# WiFi.net
KiCad netlist of a schematic drawn in Altium Designer
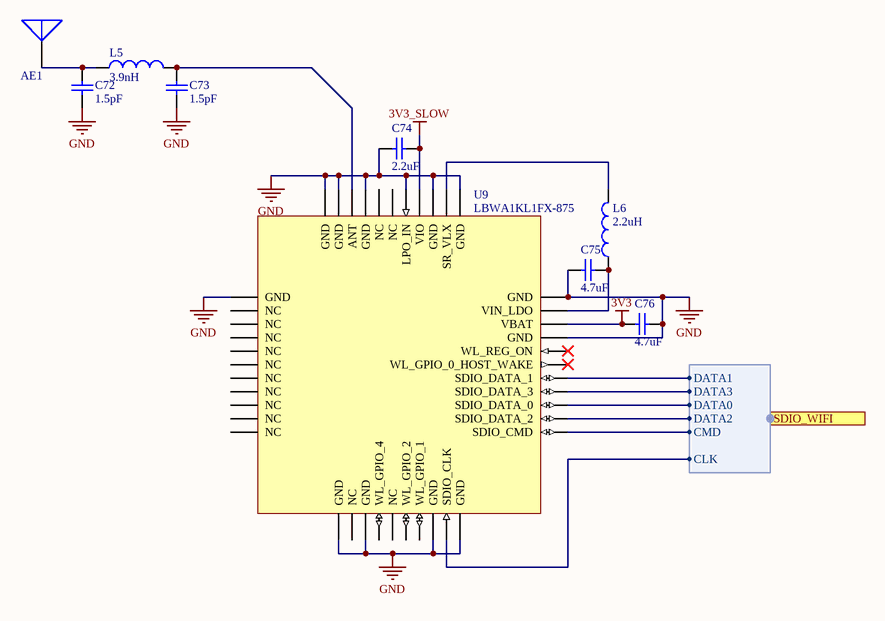
[diagram p0: WiFi.SchDoc]

(export (version "E")
  (design (tool "Eeschema 10.0.6"))
  (components
    (comp (ref "AE1")
      (value "2450AT42A100E")
      (footprint "ANTENNA (3.2x1.6MM)")
      (fields (field (name "MANUFACTURER") "Johanson Technology Inc."))
      (libsource (lib "Components") (part "2450AT42A100E"))
    )
    (comp (ref "C72")
      (value "1.5pF")
      (footprint "C0402[1005X55]")
      (description "1.5pF 50V 0.05pF 0402 (1005 Metric)")
      (fields (field (name "PARTNUMBER") "GRM1555C1H1R5WA01D") (field (name "MANUFACTURER") "Murata"))
      (libsource (lib "Capacitors") (part "CAP_1.5pF_50V_0402_0.05pF"))
    )
    (comp (ref "C73")
      (value "1.5pF")
      (footprint "C0402[1005X55]")
      (description "1.5pF 50V 0.05pF 0402 (1005 Metric)")
      (fields (field (name "PARTNUMBER") "GRM1555C1H1R5WA01D") (field (name "MANUFACTURER") "Murata"))
      (libsource (lib "Capacitors") (part "CAP_1.5pF_50V_0402_0.05pF"))
    )
    (comp (ref "C74")
      (value "2.2uF")
      (footprint "C0402[1005X55]")
      (description "2.2uF 6.3V 20% 0402 (1005 Metric)")
      (fields (field (name "PARTNUMBER") "GRM155R60J225ME15D") (field (name "MANUFACTURER") "Murata"))
      (libsource (lib "Capacitors") (part "CAP_2.2uF_6.3V_0402_20%"))
    )
    (comp (ref "C75")
      (value "4.7uF")
      (footprint "C0402[1005X55]")
      (description "4.7uF 6.3V 20% 0402 (1005 Metric)")
      (fields (field (name "PARTNUMBER") "GRM155R60J475ME47D") (field (name "MANUFACTURER") "Murata"))
      (libsource (lib "Capacitors") (part "CAP_4.7uF_6.3V_0402_20%"))
    )
    (comp (ref "C76")
      (value "4.7uF")
      (footprint "C0402[1005X55]")
      (description "4.7uF 6.3V 20% 0402 (1005 Metric)")
      (fields (field (name "PARTNUMBER") "GRM155R60J475ME47D") (field (name "MANUFACTURER") "Murata"))
      (libsource (lib "Capacitors") (part "CAP_4.7uF_6.3V_0402_20%"))
    )
    (comp (ref "L5")
      (value "3.9nH")
      (footprint "IND0402")
      (description "3.9nH +/-0.3nH 0.3A 0402")
      (fields (field (name "PARTNUMBER") "LQG15HS3N9S02D") (field (name "MANUFACTURER") "Murata"))
      (libsource (lib "Inductors") (part "IND_3.9nH_0.3A_0402_0.3nH"))
    )
    (comp (ref "L6")
      (value "2.2uH")
      (footprint "IND0603")
      (description "2.2uH 20% 750mA 0603")
      (fields (field (name "PARTNUMBER") "LQM18PZ2R2MCHD") (field (name "MANUFACTURER") "Murata"))
      (libsource (lib "Inductors") (part "IND_2.2uH_750mA_0603_20%"))
    )
    (comp (ref "U9")
      (value "LBWA1KL1FX-875")
      (footprint "LGA-42")
      (description "WI-FI-B/G/N NETWORK CONTROLLER")
      (fields (field (name "MANUFACTURER") "Murata"))
      (libsource (lib "ICs") (part "LBWA1KL1FX-875"))
    )
  )
  (nets
    (net (code "2") (name "/CLK") (class "Default")
      (node (ref "U9") (pin "20") (pinfunction "SDIO_CLK_20") (pintype "input"))
    )
    (net (code "3") (name "/CMD") (class "Default")
      (node (ref "U9") (pin "22") (pinfunction "SDIO_CMD_22") (pintype "bidirectional"))
    )
    (net (code "4") (name "/DATA0") (class "Default")
      (node (ref "U9") (pin "24") (pinfunction "SDIO_DATA_0_24") (pintype "bidirectional"))
    )
    (net (code "5") (name "/DATA1") (class "Default")
      (node (ref "U9") (pin "26") (pinfunction "SDIO_DATA_1_26") (pintype "bidirectional"))
    )
    (net (code "6") (name "/DATA2") (class "Default")
      (node (ref "U9") (pin "23") (pinfunction "SDIO_DATA_2_23") (pintype "bidirectional"))
    )
    (net (code "7") (name "/DATA3") (class "Default")
      (node (ref "U9") (pin "25") (pinfunction "SDIO_DATA_3_25") (pintype "bidirectional"))
    )
    (net (code "9") (name "3V3") (class "Default")
      (node (ref "C76") (pin "2") (pinfunction "2_2") (pintype "passive"))
      (node (ref "U9") (pin "30") (pinfunction "VBAT_30") (pintype "passive"))
    )
    (net (code "10") (name "3V3_SLOW") (class "Default")
      (node (ref "C74") (pin "1") (pinfunction "1_1") (pintype "passive"))
      (node (ref "U9") (pin "36") (pinfunction "VIO_36") (pintype "passive"))
    )
    (net (code "11") (name "GND") (class "Default")
      (node (ref "C72") (pin "1") (pinfunction "1_1") (pintype "passive"))
      (node (ref "C73") (pin "1") (pinfunction "1_1") (pintype "passive"))
      (node (ref "C74") (pin "2") (pinfunction "2_2") (pintype "passive"))
      (node (ref "C75") (pin "2") (pinfunction "2_2") (pintype "passive"))
      (node (ref "C76") (pin "1") (pinfunction "1_1") (pintype "passive"))
      (node (ref "U9") (pin "1") (pinfunction "GND_1") (pintype "passive"))
      (node (ref "U9") (pin "12") (pinfunction "GND_12") (pintype "passive"))
      (node (ref "U9") (pin "14") (pinfunction "GND_14") (pintype "passive"))
      (node (ref "U9") (pin "19") (pinfunction "GND_19") (pintype "passive"))
      (node (ref "U9") (pin "21") (pinfunction "GND_21") (pintype "passive"))
      (node (ref "U9") (pin "29") (pinfunction "GND_29") (pintype "passive"))
      (node (ref "U9") (pin "32") (pinfunction "GND_32") (pintype "passive"))
      (node (ref "U9") (pin "33") (pinfunction "GND_33") (pintype "passive"))
      (node (ref "U9") (pin "35") (pinfunction "GND_35") (pintype "passive"))
      (node (ref "U9") (pin "37") (pinfunction "LPO_IN_37") (pintype "input"))
      (node (ref "U9") (pin "40") (pinfunction "GND_40") (pintype "passive"))
      (node (ref "U9") (pin "42") (pinfunction "GND_42") (pintype "passive"))
      (node (ref "U9") (pin "43") (pinfunction "GND_43") (pintype "passive"))
    )
    (net (code "12") (name "Net-(AE1-Pad1)") (class "Default")
      (node (ref "AE1") (pin "1") (pinfunction "1_1") (pintype "passive"))
      (node (ref "C72") (pin "2") (pinfunction "2_2") (pintype "passive"))
      (node (ref "L5") (pin "1") (pinfunction "1_1") (pintype "passive"))
    )
    (net (code "13") (name "Net-(U9-ANT)") (class "Default")
      (node (ref "C73") (pin "2") (pinfunction "2_2") (pintype "passive"))
      (node (ref "L5") (pin "2") (pinfunction "2_2") (pintype "passive"))
      (node (ref "U9") (pin "41") (pinfunction "ANT_41") (pintype "passive"))
    )
    (net (code "14") (name "Net-(U9-SR_VLX)") (class "Default")
      (node (ref "L6") (pin "2") (pinfunction "2_2") (pintype "passive"))
      (node (ref "U9") (pin "34") (pinfunction "SR_VLX_34") (pintype "passive"))
    )
    (net (code "15") (name "Net-(U9-VIN_LDO)") (class "Default")
      (node (ref "C75") (pin "1") (pinfunction "1_1") (pintype "passive"))
      (node (ref "L6") (pin "1") (pinfunction "1_1") (pintype "passive"))
      (node (ref "U9") (pin "31") (pinfunction "VIN_LDO_31") (pintype "passive"))
    )
    (net (code "16") (name "unconnected-(U9-NC-Pad2)") (class "Default")
      (node (ref "U9") (pin "2") (pinfunction "NC_2") (pintype "passive"))
    )
    (net (code "17") (name "unconnected-(U9-NC-Pad3)") (class "Default")
      (node (ref "U9") (pin "3") (pinfunction "NC_3") (pintype "passive"))
    )
    (net (code "18") (name "unconnected-(U9-NC-Pad4)") (class "Default")
      (node (ref "U9") (pin "4") (pinfunction "NC_4") (pintype "passive"))
    )
    (net (code "19") (name "unconnected-(U9-NC-Pad5)") (class "Default")
      (node (ref "U9") (pin "5") (pinfunction "NC_5") (pintype "passive"))
    )
    (net (code "20") (name "unconnected-(U9-NC-Pad6)") (class "Default")
      (node (ref "U9") (pin "6") (pinfunction "NC_6") (pintype "passive"))
    )
    (net (code "21") (name "unconnected-(U9-NC-Pad7)") (class "Default")
      (node (ref "U9") (pin "7") (pinfunction "NC_7") (pintype "passive"))
    )
    (net (code "22") (name "unconnected-(U9-NC-Pad8)") (class "Default")
      (node (ref "U9") (pin "8") (pinfunction "NC_8") (pintype "passive"))
    )
    (net (code "23") (name "unconnected-(U9-NC-Pad9)") (class "Default")
      (node (ref "U9") (pin "9") (pinfunction "NC_9") (pintype "passive"))
    )
    (net (code "24") (name "unconnected-(U9-NC-Pad10)") (class "Default")
      (node (ref "U9") (pin "10") (pinfunction "NC_10") (pintype "passive"))
    )
    (net (code "25") (name "unconnected-(U9-NC-Pad11)") (class "Default")
      (node (ref "U9") (pin "11") (pinfunction "NC_11") (pintype "passive"))
    )
    (net (code "26") (name "unconnected-(U9-NC-Pad13)") (class "Default")
      (node (ref "U9") (pin "13") (pinfunction "NC_13") (pintype "passive"))
    )
    (net (code "27") (name "unconnected-(U9-NC-Pad16)") (class "Default")
      (node (ref "U9") (pin "16") (pinfunction "NC_16") (pintype "passive"))
    )
    (net (code "28") (name "unconnected-(U9-NC-Pad38)") (class "Default")
      (node (ref "U9") (pin "38") (pinfunction "NC_38") (pintype "passive"))
    )
    (net (code "29") (name "unconnected-(U9-NC-Pad39)") (class "Default")
      (node (ref "U9") (pin "39") (pinfunction "NC_39") (pintype "passive"))
    )
    (net (code "30") (name "unconnected-(U9-WL_GPIO_0_HOST_WAKE-Pad27)") (class "Default")
      (node (ref "U9") (pin "27") (pinfunction "WL_GPIO_0_HOST_WAKE_27") (pintype "output+no_connect"))
    )
    (net (code "31") (name "unconnected-(U9-WL_GPIO_1-Pad18)") (class "Default")
      (node (ref "U9") (pin "18") (pinfunction "WL_GPIO_1_18") (pintype "bidirectional"))
    )
    (net (code "32") (name "unconnected-(U9-WL_GPIO_2-Pad17)") (class "Default")
      (node (ref "U9") (pin "17") (pinfunction "WL_GPIO_2_17") (pintype "bidirectional"))
    )
    (net (code "33") (name "unconnected-(U9-WL_GPIO_4-Pad15)") (class "Default")
      (node (ref "U9") (pin "15") (pinfunction "WL_GPIO_4_15") (pintype "bidirectional"))
    )
    (net (code "34") (name "unconnected-(U9-WL_REG_ON-Pad28)") (class "Default")
      (node (ref "U9") (pin "28") (pinfunction "WL_REG_ON_28") (pintype "input+no_connect"))
    )
  )
)
